# CH32V003F4P6_Dev_Kit_DIY_V1_0.net
KiCad netlist of a schematic drawn in Altium Designer
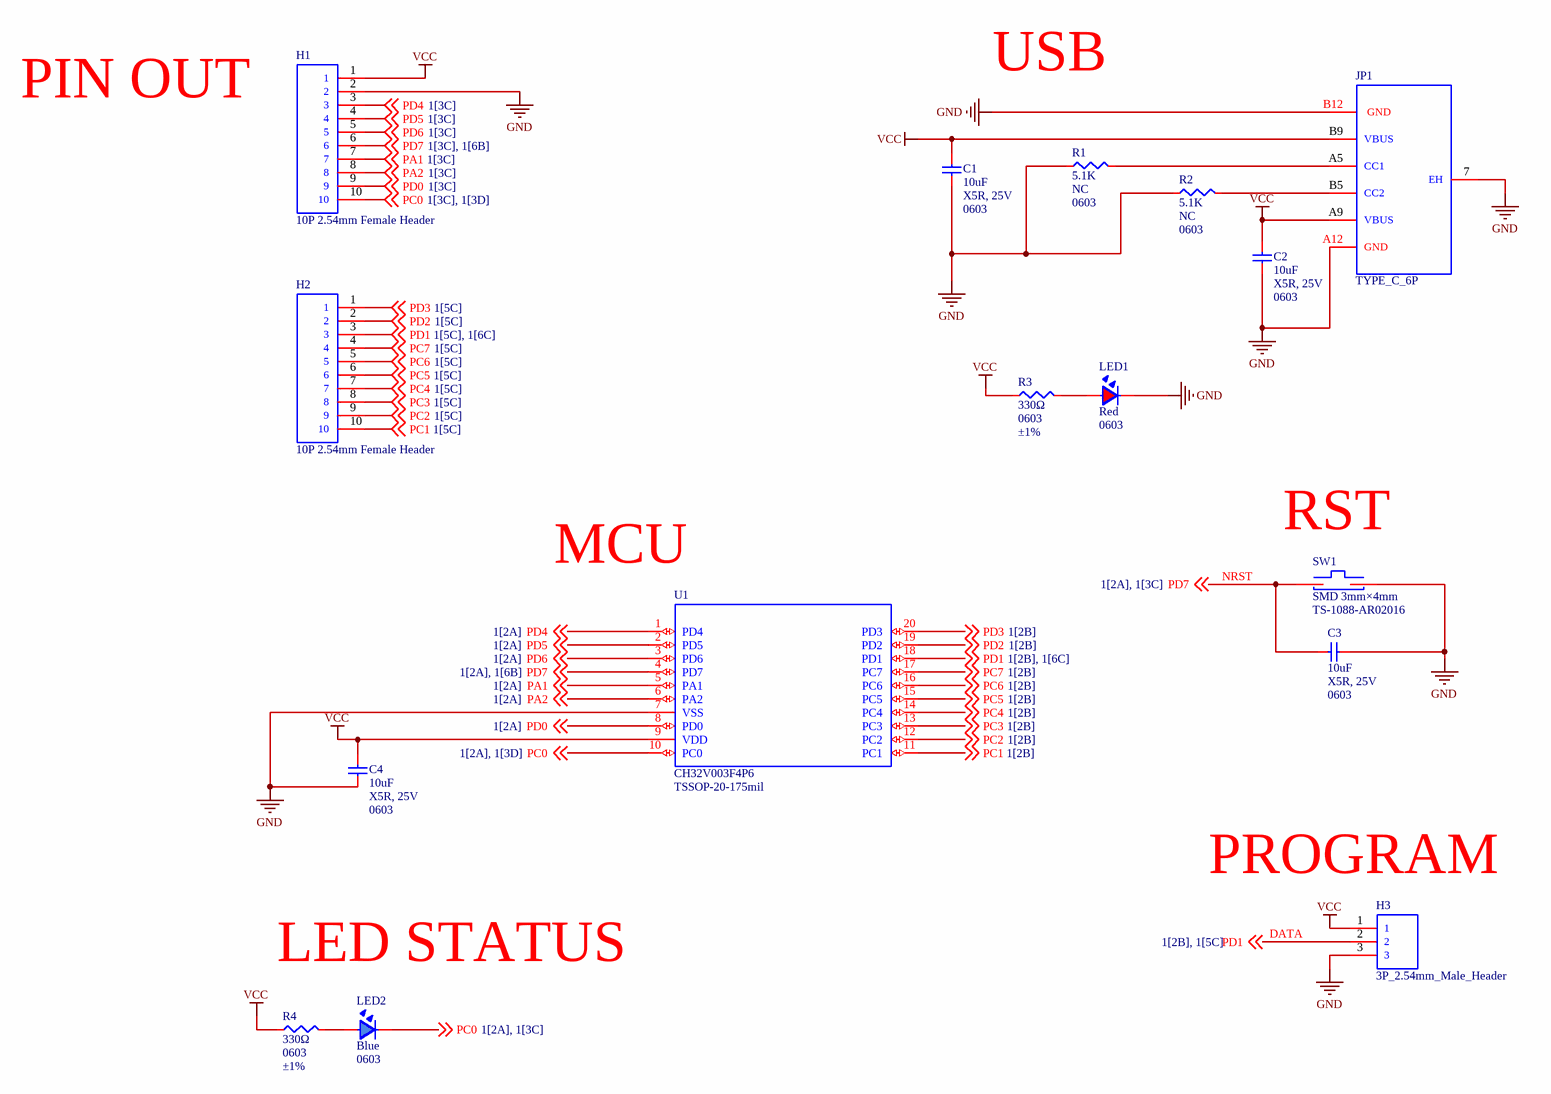
[diagram p0: CH32V003F4P6_Dev_Kit_DIY_V1.0.SchDoc]

(export (version "E")
  (design (tool "Eeschema 10.0.6"))
  (components
    (comp (ref "C1")
      (value "10uF")
      (footprint "C0603")
      (description "25V 10uF X5R ±20% 0603 Multilayer Ceramic Capacitors MLCC - SMD/SMT ROHS")
      (fields
        (field (name "MANUFACTURER") "YAGEO")
        (field (name "MFR. PART") "CC0603MRX5R8BB106")
        (field (name "TEMPERATURE COEFFICIENT") "X5R, 25V")
        (field (name "PACKAGE") "0603")
      )
      (libsource (lib "Capacitor") (part "C0603_MLCC_10uF_X5R_25V"))
    )
    (comp (ref "C2")
      (value "10uF")
      (footprint "C0603")
      (description "25V 10uF X5R ±20% 0603 Multilayer Ceramic Capacitors MLCC - SMD/SMT ROHS")
      (fields
        (field (name "MANUFACTURER") "YAGEO")
        (field (name "MFR. PART") "CC0603MRX5R8BB106")
        (field (name "TEMPERATURE COEFFICIENT") "X5R, 25V")
        (field (name "PACKAGE") "0603")
      )
      (libsource (lib "Capacitor") (part "C0603_MLCC_10uF_X5R_25V"))
    )
    (comp (ref "C3")
      (value "10uF")
      (footprint "C0603")
      (description "25V 10uF X5R ±20% 0603 Multilayer Ceramic Capacitors MLCC - SMD/SMT ROHS")
      (fields
        (field (name "MANUFACTURER") "YAGEO")
        (field (name "MFR. PART") "CC0603MRX5R8BB106")
        (field (name "TEMPERATURE COEFFICIENT") "X5R, 25V")
        (field (name "PACKAGE") "0603")
      )
      (libsource (lib "Capacitor") (part "C0603_MLCC_10uF_X5R_25V"))
    )
    (comp (ref "C4")
      (value "10uF")
      (footprint "C0603")
      (description "25V 10uF X5R ±20% 0603 Multilayer Ceramic Capacitors MLCC - SMD/SMT ROHS")
      (fields
        (field (name "MANUFACTURER") "YAGEO")
        (field (name "MFR. PART") "CC0603MRX5R8BB106")
        (field (name "TEMPERATURE COEFFICIENT") "X5R, 25V")
        (field (name "PACKAGE") "0603")
      )
      (libsource (lib "Capacitor") (part "C0603_MLCC_10uF_X5R_25V"))
    )
    (comp (ref "H1")
      (value "10P 2.54mm Female Header")
      (footprint "10P, 2,54mm, FEMALE HEADER")
      (description "2.54mm 1 8P Through Hole 1x8P Through Hole,P=2.54mm Female Headers ROHS")
      (fields (field (name "MANUFACTURER") "ZHOURI") (field (name "MFR. PART") "PM2.54-1*10"))
      (libsource (lib "HEADER") (part "10P 2.54mm Female Header"))
    )
    (comp (ref "H2")
      (value "10P 2.54mm Female Header")
      (footprint "10P, 2,54mm, FEMALE HEADER")
      (description "2.54mm 1 8P Through Hole 1x8P Through Hole,P=2.54mm Female Headers ROHS")
      (fields (field (name "MANUFACTURER") "ZHOURI") (field (name "MFR. PART") "PM2.54-1*10"))
      (libsource (lib "HEADER") (part "10P 2.54mm Female Header"))
    )
    (comp (ref "H3")
      (value "3P_2.54mm_Male_Header")
      (footprint "3P_2.54mm_Male_Header")
      (fields
        (field (name "MANUFACTURER") "XFCN")
        (field (name "MFR. PART") "PZ254V-11-03P")
        (field (name "LCSC PART") "C2937625")
      )
      (libsource (lib "HEADER") (part "3P_2.54mm_Male_Header"))
    )
    (comp (ref "JP1")
      (value "TYPE_C_6P")
      (footprint "TYPE_C_6P")
      (description "3A USB 3.1 1 Surface Mount, Right Angle 6P Female -40℃~+85℃ Type-C SMD USB Connectors ROHS")
      (fields (field (name "MANUFACTURER") "SHOU HAN") (field (name "MFR. PART") "TYPE-C 6P"))
      (libsource (lib "CONNECTER") (part "TYPE_C_6P"))
    )
    (comp (ref "LED1")
      (value "Red")
      (footprint "LED0603_RED")
      (description "20mA 230mcd Water Clear -40℃~+85℃ 630nm Red 120° 75mW 1.95V 0603 LED Indication - Discrete ROHS")
      (fields
        (field (name "MANUFACTURER") "Kingbright")
        (field (name "MFR. PART") "APT1608SURCK")
        (field (name "PACKAGE") "0603")
      )
      (libsource (lib "LED") (part "LED0603_Red"))
    )
    (comp (ref "LED2")
      (value "Blue")
      (footprint "LED0603_BLUE")
      (description "2mA 24mcd Water Clear -40℃~+85℃ 470nm Blue 130° 120mW 2.65V 0603 LED Indication - Discrete ROHS")
      (fields
        (field (name "MANUFACTURER") "Kingbright")
        (field (name "MFR. PART") "APT1608LVBC/D")
        (field (name "PACKAGE") "0603")
      )
      (libsource (lib "LED") (part "LED0603_Blue"))
    )
    (comp (ref "R1")
      (value "5.1K")
      (footprint "R0603 - NC")
      (fields (field (name "STATUS") "NC") (field (name "PACKAGE") "0603"))
      (libsource (lib "Resistor") (part "R0603_NC"))
    )
    (comp (ref "R2")
      (value "5.1K")
      (footprint "R0603 - NC")
      (fields (field (name "STATUS") "NC") (field (name "PACKAGE") "0603"))
      (libsource (lib "Resistor") (part "R0603_NC"))
    )
    (comp (ref "R3")
      (value "330Ω")
      (footprint "R0603")
      (description "100mW Thick Film Resistor 75V ±100ppm/℃ ±1% 330Ω 0603 Chip Resistor - Surface Mount ROHS")
      (fields
        (field (name "MANUFACTURER") "YAGEO")
        (field (name "MFR. PART") "RC0603FR-07330RL")
        (field (name "PACKAGE") "0603")
        (field (name "TOLERANCE") "±1%")
      )
      (libsource (lib "Resistor") (part "R0603_330Ω_±1%"))
    )
    (comp (ref "R4")
      (value "330Ω")
      (footprint "R0603")
      (description "100mW Thick Film Resistor 75V ±100ppm/℃ ±1% 330Ω 0603 Chip Resistor - Surface Mount ROHS")
      (fields
        (field (name "MANUFACTURER") "YAGEO")
        (field (name "MFR. PART") "RC0603FR-07330RL")
        (field (name "PACKAGE") "0603")
        (field (name "TOLERANCE") "±1%")
      )
      (libsource (lib "Resistor") (part "R0603_330Ω_±1%"))
    )
    (comp (ref "SW1")
      (value "SMD 3mm×4mm")
      (footprint "ROUND_BUTTON_SMD 3*4mm")
      (fields
        (field (name "MANUFACTURER") "XUNPU")
        (field (name "LCSC PART") "C720477")
        (field (name "MFR. PART") "TS-1088-AR02016")
      )
      (libsource (lib "BUTTON and SWITCH") (part "SW_BUTTON_SMD_3mm×4mm"))
    )
    (comp (ref "U1")
      (value "CH32V003F4P6")
      (footprint "TSSOP-20")
      (description "TSSOP-20-175mil Microcontrollers (MCU/MPU/SOC) ROHS")
      (fields
        (field (name "MANUFACTURER") "WCH")
        (field (name "LCSC PART") "C5187096")
        (field (name "PACKAGE") "TSSOP-20-175mil")
      )
      (libsource (lib "MCU") (part "CH32V003F4P6_TSSOP-20-175mil"))
    )
  )
  (nets
    (net (code "1") (name "GND") (class "Default")
      (node (ref "C1") (pin "2") (pinfunction "2_2") (pintype "passive"))
      (node (ref "C2") (pin "1") (pinfunction "1_1") (pintype "passive"))
      (node (ref "C3") (pin "2") (pinfunction "2_2") (pintype "passive"))
      (node (ref "C4") (pin "1") (pinfunction "1_1") (pintype "passive"))
      (node (ref "H1") (pin "2") (pinfunction "2_2") (pintype "passive"))
      (node (ref "H3") (pin "3") (pinfunction "3_3") (pintype "passive"))
      (node (ref "JP1") (pin "7") (pinfunction "EH_7") (pintype "passive"))
      (node (ref "JP1") (pin "A12") (pinfunction "GND_A12") (pintype "passive"))
      (node (ref "JP1") (pin "B12") (pinfunction "_GND_B12") (pintype "passive"))
      (node (ref "LED1") (pin "2") (pinfunction "2_2") (pintype "passive"))
      (node (ref "R1") (pin "1") (pinfunction "1_1") (pintype "passive"))
      (node (ref "R2") (pin "1") (pinfunction "1_1") (pintype "passive"))
      (node (ref "SW1") (pin "2") (pinfunction "2_2") (pintype "passive"))
      (node (ref "U1") (pin "7") (pinfunction "VSS_7") (pintype "power_in"))
    )
    (net (code "2") (name "Net-(JP1-CC1)") (class "Default")
      (node (ref "JP1") (pin "A5") (pinfunction "CC1_A5") (pintype "passive"))
      (node (ref "R1") (pin "2") (pinfunction "2_2") (pintype "passive"))
    )
    (net (code "3") (name "Net-(JP1-CC2)") (class "Default")
      (node (ref "JP1") (pin "B5") (pinfunction "CC2_B5") (pintype "passive"))
      (node (ref "R2") (pin "2") (pinfunction "2_2") (pintype "passive"))
    )
    (net (code "4") (name "Net-(LED1-Pad1)") (class "Default")
      (node (ref "LED1") (pin "1") (pinfunction "1_1") (pintype "passive"))
      (node (ref "R3") (pin "2") (pinfunction "2_2") (pintype "passive"))
    )
    (net (code "5") (name "Net-(LED2-Pad1)") (class "Default")
      (node (ref "LED2") (pin "1") (pinfunction "1_1") (pintype "passive"))
      (node (ref "R4") (pin "2") (pinfunction "2_2") (pintype "passive"))
    )
    (net (code "6") (name "PA1") (class "Default")
      (node (ref "H1") (pin "7") (pinfunction "7_7") (pintype "passive"))
      (node (ref "U1") (pin "5") (pinfunction "PA1_5") (pintype "bidirectional"))
    )
    (net (code "7") (name "PA2") (class "Default")
      (node (ref "H1") (pin "8") (pinfunction "8_8") (pintype "passive"))
      (node (ref "U1") (pin "6") (pinfunction "PA2_6") (pintype "bidirectional"))
    )
    (net (code "8") (name "PC0") (class "Default")
      (node (ref "H1") (pin "10") (pinfunction "10_10") (pintype "passive"))
      (node (ref "LED2") (pin "2") (pinfunction "2_2") (pintype "passive"))
      (node (ref "U1") (pin "10") (pinfunction "PC0_10") (pintype "bidirectional"))
    )
    (net (code "9") (name "PC1") (class "Default")
      (node (ref "H2") (pin "10") (pinfunction "10_10") (pintype "passive"))
      (node (ref "U1") (pin "11") (pinfunction "PC1_11") (pintype "bidirectional"))
    )
    (net (code "10") (name "PC2") (class "Default")
      (node (ref "H2") (pin "9") (pinfunction "9_9") (pintype "passive"))
      (node (ref "U1") (pin "12") (pinfunction "PC2_12") (pintype "bidirectional"))
    )
    (net (code "11") (name "PC3") (class "Default")
      (node (ref "H2") (pin "8") (pinfunction "8_8") (pintype "passive"))
      (node (ref "U1") (pin "13") (pinfunction "PC3_13") (pintype "bidirectional"))
    )
    (net (code "12") (name "PC4") (class "Default")
      (node (ref "H2") (pin "7") (pinfunction "7_7") (pintype "passive"))
      (node (ref "U1") (pin "14") (pinfunction "PC4_14") (pintype "bidirectional"))
    )
    (net (code "13") (name "PC5") (class "Default")
      (node (ref "H2") (pin "6") (pinfunction "6_6") (pintype "passive"))
      (node (ref "U1") (pin "15") (pinfunction "PC5_15") (pintype "bidirectional"))
    )
    (net (code "14") (name "PC6") (class "Default")
      (node (ref "H2") (pin "5") (pinfunction "5_5") (pintype "passive"))
      (node (ref "U1") (pin "16") (pinfunction "PC6_16") (pintype "bidirectional"))
    )
    (net (code "15") (name "PC7") (class "Default")
      (node (ref "H2") (pin "4") (pinfunction "4_4") (pintype "passive"))
      (node (ref "U1") (pin "17") (pinfunction "PC7_17") (pintype "bidirectional"))
    )
    (net (code "16") (name "PD0") (class "Default")
      (node (ref "H1") (pin "9") (pinfunction "9_9") (pintype "passive"))
      (node (ref "U1") (pin "8") (pinfunction "PD0_8") (pintype "bidirectional"))
    )
    (net (code "17") (name "PD1") (class "Default")
      (node (ref "H2") (pin "3") (pinfunction "3_3") (pintype "passive"))
      (node (ref "H3") (pin "2") (pinfunction "2_2") (pintype "passive"))
      (node (ref "U1") (pin "18") (pinfunction "PD1_18") (pintype "bidirectional"))
    )
    (net (code "18") (name "PD2") (class "Default")
      (node (ref "H2") (pin "2") (pinfunction "2_2") (pintype "passive"))
      (node (ref "U1") (pin "19") (pinfunction "PD2_19") (pintype "bidirectional"))
    )
    (net (code "19") (name "PD3") (class "Default")
      (node (ref "H2") (pin "1") (pinfunction "1_1") (pintype "passive"))
      (node (ref "U1") (pin "20") (pinfunction "PD3_20") (pintype "bidirectional"))
    )
    (net (code "20") (name "PD4") (class "Default")
      (node (ref "H1") (pin "3") (pinfunction "3_3") (pintype "passive"))
      (node (ref "U1") (pin "1") (pinfunction "PD4_1") (pintype "bidirectional"))
    )
    (net (code "21") (name "PD5") (class "Default")
      (node (ref "H1") (pin "4") (pinfunction "4_4") (pintype "passive"))
      (node (ref "U1") (pin "2") (pinfunction "PD5_2") (pintype "bidirectional"))
    )
    (net (code "22") (name "PD6") (class "Default")
      (node (ref "H1") (pin "5") (pinfunction "5_5") (pintype "passive"))
      (node (ref "U1") (pin "3") (pinfunction "PD6_3") (pintype "bidirectional"))
    )
    (net (code "23") (name "PD7") (class "Default")
      (node (ref "C3") (pin "1") (pinfunction "1_1") (pintype "passive"))
      (node (ref "H1") (pin "6") (pinfunction "6_6") (pintype "passive"))
      (node (ref "SW1") (pin "1") (pinfunction "1_1") (pintype "passive"))
      (node (ref "U1") (pin "4") (pinfunction "PD7_4") (pintype "bidirectional"))
    )
    (net (code "24") (name "VCC") (class "Default")
      (node (ref "C1") (pin "1") (pinfunction "1_1") (pintype "passive"))
      (node (ref "C2") (pin "2") (pinfunction "2_2") (pintype "passive"))
      (node (ref "C4") (pin "2") (pinfunction "2_2") (pintype "passive"))
      (node (ref "H1") (pin "1") (pinfunction "1_1") (pintype "passive"))
      (node (ref "H3") (pin "1") (pinfunction "1_1") (pintype "passive"))
      (node (ref "JP1") (pin "A9") (pinfunction "VBUS_A9") (pintype "passive"))
      (node (ref "JP1") (pin "B9") (pinfunction "VBUS_B9") (pintype "passive"))
      (node (ref "R3") (pin "1") (pinfunction "1_1") (pintype "passive"))
      (node (ref "R4") (pin "1") (pinfunction "1_1") (pintype "passive"))
      (node (ref "U1") (pin "9") (pinfunction "VDD_9") (pintype "power_in"))
    )
  )
)
